# 06_POWER_3.net
KiCad netlist of a schematic drawn in Altium Designer
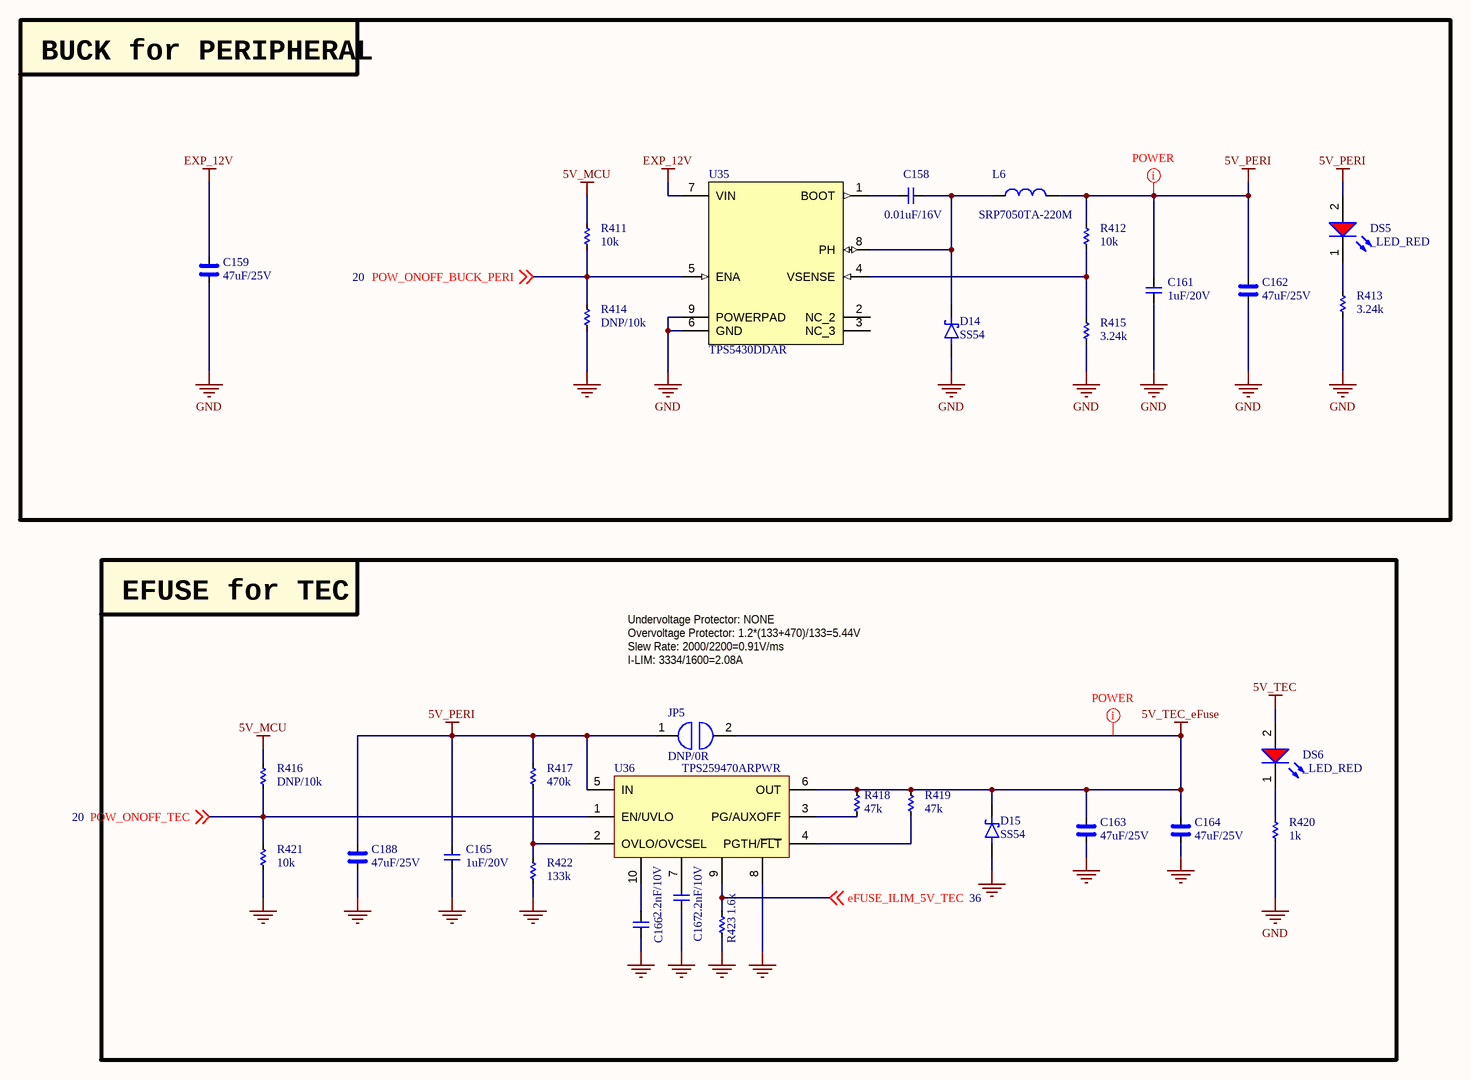
[diagram p0: 06_POWER_3.SchDoc]

(export (version "E")
  (design (tool "Eeschema 10.0.6"))
  (components
    (comp (ref "C158")
      (value "0.01uF/16V")
      (footprint "CAP_C_1608X80")
      (description "CAP")
      (libsource (lib "LABLIB") (part "_CAP_C_2"))
    )
    (comp (ref "C159")
      (value "47uF/25V")
      (footprint "CAP_C_3225X80")
      (description "CAP High Value")
      (libsource (lib "LABLIB") (part "_CAP_C_High_2"))
    )
    (comp (ref "C161")
      (value "1uF/20V")
      (footprint "CAP_C_1005X60")
      (description "CAP")
      (libsource (lib "LABLIB") (part "_CAP_C_2"))
    )
    (comp (ref "C162")
      (value "47uF/25V")
      (footprint "CAP_C_3225X80")
      (description "CAP High Value")
      (libsource (lib "LABLIB") (part "_CAP_C_High_2"))
    )
    (comp (ref "C163")
      (value "47uF/25V")
      (footprint "CAP_C_3225X80")
      (description "CAP High Value")
      (libsource (lib "LABLIB") (part "_CAP_C_High_2"))
    )
    (comp (ref "C164")
      (value "47uF/25V")
      (footprint "CAP_C_3225X80")
      (description "CAP High Value")
      (libsource (lib "LABLIB") (part "_CAP_C_High_2"))
    )
    (comp (ref "C165")
      (value "1uF/20V")
      (footprint "CAP_C_1005X60")
      (description "CAP")
      (libsource (lib "LABLIB") (part "_CAP_C_2"))
    )
    (comp (ref "C166")
      (value "2.2nF/10V")
      (footprint "CAP_C_1005X60")
      (description "CAP")
      (libsource (lib "LABLIB") (part "_CAP_C_2"))
    )
    (comp (ref "C167")
      (value "2.2nF/10V")
      (footprint "CAP_C_1005X60")
      (description "CAP")
      (libsource (lib "LABLIB") (part "_CAP_C_2"))
    )
    (comp (ref "C188")
      (value "47uF/25V")
      (footprint "CAP_C_3225X80")
      (description "CAP High Value")
      (libsource (lib "LABLIB") (part "_CAP_C_High_2"))
    )
    (comp (ref "D14")
      (value "SS54")
      (footprint "DO-214AC_SMA")
      (description "DIODE SCHOTTKY")
      (libsource (lib "LABLIB") (part "DIODE SCHOTTKY"))
    )
    (comp (ref "D15")
      (value "SS54")
      (footprint "DO-214AC_SMA")
      (description "DIODE SCHOTTKY")
      (libsource (lib "LABLIB") (part "DIODE SCHOTTKY"))
    )
    (comp (ref "DS5") (value "_LED_RED") (footprint "LED_0603") (libsource (lib "LABLIB") (part "_LED_RED")))
    (comp (ref "DS6") (value "_LED_RED") (footprint "LED_0603") (libsource (lib "LABLIB") (part "_LED_RED")))
    (comp (ref "JP5") (value "DNP/0R") (footprint "JUMPER_1608") (libsource (lib "EXP_V1") (part "JUMPER")))
    (comp (ref "L6")
      (value "SRP7050TA-220M")
      (footprint "PSM6050")
      (description "FIXED IND 22UH 2.5A 170 MOHM SMD")
      (libsource (lib "LABLIB") (part "SRP7050TA-220M"))
    )
    (comp (ref "R411")
      (value "10k")
      (footprint "RES_C_1005X40")
      (description "RES")
      (libsource (lib "LABLIB") (part "_RES_B_2"))
    )
    (comp (ref "R412")
      (value "10k")
      (footprint "RES_C_1005X40")
      (description "RES")
      (libsource (lib "LABLIB") (part "_RES_B_2"))
    )
    (comp (ref "R413")
      (value "3.24k")
      (footprint "RES_C_1005X40")
      (description "RES")
      (libsource (lib "LABLIB") (part "_RES_B_2"))
    )
    (comp (ref "R414")
      (value "DNP/10k")
      (footprint "RES_C_1005X40")
      (description "RES")
      (libsource (lib "LABLIB") (part "_RES_B_2"))
    )
    (comp (ref "R415")
      (value "3.24k")
      (footprint "RES_C_1005X40")
      (description "RES")
      (libsource (lib "LABLIB") (part "_RES_B_2"))
    )
    (comp (ref "R416")
      (value "DNP/10k")
      (footprint "RES_C_1005X40")
      (description "RES")
      (libsource (lib "LABLIB") (part "_RES_B_2"))
    )
    (comp (ref "R417")
      (value "470k")
      (footprint "RES_C_1005X40")
      (description "RES")
      (libsource (lib "LABLIB") (part "_RES_B_2"))
    )
    (comp (ref "R418")
      (value "47k")
      (footprint "RES_C_1005X40")
      (description "RES")
      (libsource (lib "LABLIB") (part "_RES_B_2"))
    )
    (comp (ref "R419")
      (value "47k")
      (footprint "RES_C_1005X40")
      (description "RES")
      (libsource (lib "LABLIB") (part "_RES_B_2"))
    )
    (comp (ref "R420")
      (value "1k")
      (footprint "RES_C_1005X40")
      (description "RES")
      (libsource (lib "LABLIB") (part "_RES_B_2"))
    )
    (comp (ref "R421")
      (value "10k")
      (footprint "RES_C_1005X40")
      (description "RES")
      (libsource (lib "LABLIB") (part "_RES_B_2"))
    )
    (comp (ref "R422")
      (value "133k")
      (footprint "RES_C_1005X40")
      (description "RES")
      (libsource (lib "LABLIB") (part "_RES_B_2"))
    )
    (comp (ref "R423")
      (value "1.6k")
      (footprint "RES_C_1005X40")
      (description "RES")
      (libsource (lib "LABLIB") (part "_RES_B_2"))
    )
    (comp (ref "U35")
      (value "TPS5430DDAR")
      (footprint "TPS54531DDAR")
      (description "IC REG BUCK ADJ 3A 8SOPWR")
      (libsource (lib "EXP_HW_V3") (part "TPS5430DDAR"))
    )
    (comp (ref "U36")
      (value "TPS259470ARPWR")
      (footprint "VQFN-HR-10")
      (libsource (lib "EXP_HW_V3") (part "TPS259470ARPWR"))
    )
  )
  (nets
    (net (code "1") (name "5V_MCU") (class "Default")
      (node (ref "R411") (pin "1") (pinfunction "1_1") (pintype "passive"))
      (node (ref "R416") (pin "1") (pinfunction "1_1") (pintype "passive"))
    )
    (net (code "2") (name "5V_PERI") (class "Default")
      (node (ref "C161") (pin "2") (pinfunction "2_2") (pintype "passive"))
      (node (ref "C162") (pin "2") (pinfunction "2_2") (pintype "passive"))
      (node (ref "C165") (pin "2") (pinfunction "2_2") (pintype "passive"))
      (node (ref "C188") (pin "2") (pinfunction "2_2") (pintype "passive"))
      (node (ref "DS5") (pin "2") (pinfunction "A_2") (pintype "passive"))
      (node (ref "JP5") (pin "1") (pinfunction "1_1") (pintype "passive"))
      (node (ref "L6") (pin "2") (pinfunction "2_2") (pintype "passive"))
      (node (ref "R412") (pin "2") (pinfunction "2_2") (pintype "passive"))
      (node (ref "R417") (pin "2") (pinfunction "2_2") (pintype "passive"))
      (node (ref "U36") (pin "5") (pinfunction "IN_5") (pintype "passive"))
    )
    (net (code "3") (name "5V_TEC") (class "Default")
      (node (ref "DS6") (pin "2") (pinfunction "A_2") (pintype "passive"))
    )
    (net (code "4") (name "5V_TEC_eFuse") (class "Default")
      (node (ref "C163") (pin "2") (pinfunction "2_2") (pintype "passive"))
      (node (ref "C164") (pin "2") (pinfunction "2_2") (pintype "passive"))
      (node (ref "D15") (pin "1") (pinfunction "K_1") (pintype "passive"))
      (node (ref "JP5") (pin "2") (pinfunction "2_2") (pintype "passive"))
      (node (ref "R418") (pin "2") (pinfunction "2_2") (pintype "passive"))
      (node (ref "R419") (pin "2") (pinfunction "2_2") (pintype "passive"))
      (node (ref "U36") (pin "6") (pinfunction "OUT_6") (pintype "passive"))
    )
    (net (code "5") (name "EXP_12V") (class "Default")
      (node (ref "C159") (pin "2") (pinfunction "2_2") (pintype "passive"))
      (node (ref "U35") (pin "7") (pinfunction "VIN_7") (pintype "power_in"))
    )
    (net (code "6") (name "GND") (class "Default")
      (node (ref "C159") (pin "1") (pinfunction "1_1") (pintype "passive"))
      (node (ref "C161") (pin "1") (pinfunction "1_1") (pintype "passive"))
      (node (ref "C162") (pin "1") (pinfunction "1_1") (pintype "passive"))
      (node (ref "C163") (pin "1") (pinfunction "1_1") (pintype "passive"))
      (node (ref "C164") (pin "1") (pinfunction "1_1") (pintype "passive"))
      (node (ref "C165") (pin "1") (pinfunction "1_1") (pintype "passive"))
      (node (ref "C166") (pin "1") (pinfunction "1_1") (pintype "passive"))
      (node (ref "C167") (pin "1") (pinfunction "1_1") (pintype "passive"))
      (node (ref "C188") (pin "1") (pinfunction "1_1") (pintype "passive"))
      (node (ref "D14") (pin "2") (pinfunction "A_2") (pintype "passive"))
      (node (ref "D15") (pin "2") (pinfunction "A_2") (pintype "passive"))
      (node (ref "R413") (pin "1") (pinfunction "1_1") (pintype "passive"))
      (node (ref "R414") (pin "2") (pinfunction "2_2") (pintype "passive"))
      (node (ref "R415") (pin "1") (pinfunction "1_1") (pintype "passive"))
      (node (ref "R420") (pin "1") (pinfunction "1_1") (pintype "passive"))
      (node (ref "R421") (pin "2") (pinfunction "2_2") (pintype "passive"))
      (node (ref "R422") (pin "1") (pinfunction "1_1") (pintype "passive"))
      (node (ref "R423") (pin "1") (pinfunction "1_1") (pintype "passive"))
      (node (ref "U35") (pin "6") (pinfunction "GND_6") (pintype "power_in"))
      (node (ref "U35") (pin "9") (pinfunction "POWERPAD_9") (pintype "power_in"))
      (node (ref "U36") (pin "8") (pinfunction "8_8") (pintype "passive"))
    )
    (net (code "7") (name "Net-(C166-Pad2)") (class "Default")
      (node (ref "C166") (pin "2") (pinfunction "2_2") (pintype "passive"))
      (node (ref "U36") (pin "10") (pinfunction "10_10") (pintype "passive"))
    )
    (net (code "8") (name "Net-(C167-Pad2)") (class "Default")
      (node (ref "C167") (pin "2") (pinfunction "2_2") (pintype "passive"))
      (node (ref "U36") (pin "7") (pinfunction "7_7") (pintype "passive"))
    )
    (net (code "9") (name "Net-(D14-K)") (class "Default")
      (node (ref "C158") (pin "1") (pinfunction "1_1") (pintype "passive"))
      (node (ref "D14") (pin "1") (pinfunction "K_1") (pintype "passive"))
      (node (ref "L6") (pin "1") (pinfunction "1_1") (pintype "passive"))
      (node (ref "U35") (pin "8") (pinfunction "PH_8") (pintype "bidirectional"))
    )
    (net (code "10") (name "Net-(DS5-K)") (class "Default")
      (node (ref "DS5") (pin "1") (pinfunction "K_1") (pintype "passive"))
      (node (ref "R413") (pin "2") (pinfunction "2_2") (pintype "passive"))
    )
    (net (code "11") (name "Net-(DS6-K)") (class "Default")
      (node (ref "DS6") (pin "1") (pinfunction "K_1") (pintype "passive"))
      (node (ref "R420") (pin "2") (pinfunction "2_2") (pintype "passive"))
    )
    (net (code "12") (name "Net-(U35-BOOT)") (class "Default")
      (node (ref "C158") (pin "2") (pinfunction "2_2") (pintype "passive"))
      (node (ref "U35") (pin "1") (pinfunction "BOOT_1") (pintype "output"))
    )
    (net (code "13") (name "Net-(U35-VSENSE)") (class "Default")
      (node (ref "R412") (pin "1") (pinfunction "1_1") (pintype "passive"))
      (node (ref "R415") (pin "2") (pinfunction "2_2") (pintype "passive"))
      (node (ref "U35") (pin "4") (pinfunction "VSENSE_4") (pintype "input"))
    )
    (net (code "14") (name "Net-(U36-OVLO{slash}OVCSEL)") (class "Default")
      (node (ref "R417") (pin "1") (pinfunction "1_1") (pintype "passive"))
      (node (ref "R422") (pin "2") (pinfunction "2_2") (pintype "passive"))
      (node (ref "U36") (pin "2") (pinfunction "OVLO/OVCSEL_2") (pintype "passive"))
    )
    (net (code "15") (name "Net-(U36-PGTH{slash}~{FLT})") (class "Default")
      (node (ref "R419") (pin "1") (pinfunction "1_1") (pintype "passive"))
      (node (ref "U36") (pin "4") (pinfunction "PGTH/~{FLT}_4") (pintype "passive"))
    )
    (net (code "16") (name "Net-(U36-PG{slash}AUXOFF)") (class "Default")
      (node (ref "R418") (pin "1") (pinfunction "1_1") (pintype "passive"))
      (node (ref "U36") (pin "3") (pinfunction "PG/AUXOFF_3") (pintype "passive"))
    )
    (net (code "17") (name "POW_ONOFF_BUCK_PERI") (class "Default")
      (node (ref "R411") (pin "2") (pinfunction "2_2") (pintype "passive"))
      (node (ref "R414") (pin "1") (pinfunction "1_1") (pintype "passive"))
      (node (ref "U35") (pin "5") (pinfunction "ENA_5") (pintype "input"))
    )
    (net (code "18") (name "POW_ONOFF_TEC") (class "Default")
      (node (ref "R416") (pin "2") (pinfunction "2_2") (pintype "passive"))
      (node (ref "R421") (pin "1") (pinfunction "1_1") (pintype "passive"))
      (node (ref "U36") (pin "1") (pinfunction "EN/UVLO_1") (pintype "passive"))
    )
    (net (code "19") (name "eFUSE_ILIM_5V_TEC") (class "Default")
      (node (ref "R423") (pin "2") (pinfunction "2_2") (pintype "passive"))
      (node (ref "U36") (pin "9") (pinfunction "9_9") (pintype "passive"))
    )
    (net (code "20") (name "unconnected-(U35-NC_2-Pad2)") (class "Default")
      (node (ref "U35") (pin "2") (pinfunction "NC_2_2") (pintype "passive"))
    )
    (net (code "21") (name "unconnected-(U35-NC_3-Pad3)") (class "Default")
      (node (ref "U35") (pin "3") (pinfunction "NC_3_3") (pintype "passive"))
    )
  )
)
